# DS172-1_0-A.net
KiCad netlist of a schematic drawn in Altium Designer
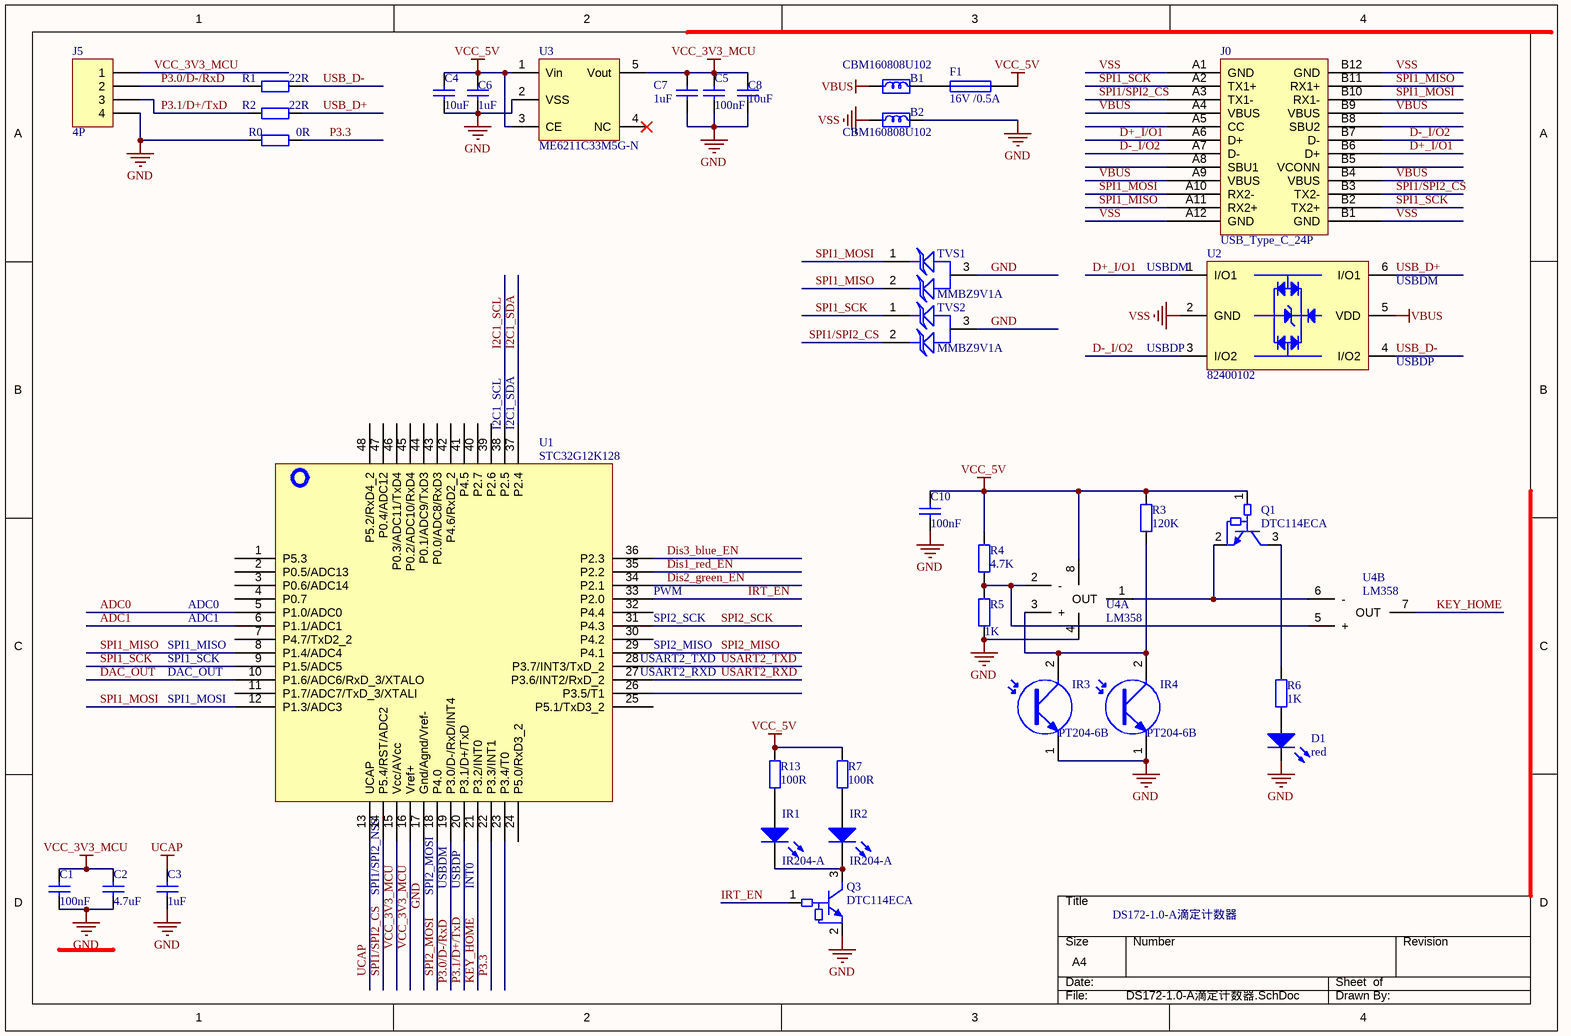
[diagram p0: DS172-1.0-A滴定计数器.SchDoc]

(export (version "E")
  (design (tool "Eeschema 10.0.6"))
  (components
    (comp (ref "B1")
      (value "CBM160808U102")
      (footprint "0603Bead")
      (description "贴片磁珠")
      (libsource (lib "AD_SCH") (part "Chip Ferrite Bead 0606"))
    )
    (comp (ref "B2")
      (value "CBM160808U102")
      (footprint "0603Bead")
      (description "贴片磁珠")
      (libsource (lib "AD_SCH") (part "Chip Ferrite Bead 0606"))
    )
    (comp (ref "C1")
      (value "100nF")
      (footprint "0603CAP")
      (description "贴片电容")
      (fields (field (name "Comment") "SMDCAP00013"))
      (libsource (lib "AD_SCH") (part "MLCC 100nF 50V ±10％ 0603"))
    )
    (comp (ref "C2")
      (value "4.7uF")
      (footprint "0603CAP")
      (description "贴片电容")
      (fields (field (name "Comment") "SMDCAP00012"))
      (libsource (lib "AD_SCH") (part "MLCC 4.7uF 50V ±10％ 0603"))
    )
    (comp (ref "C3")
      (value "1uF")
      (footprint "0603CAP")
      (description "贴片电容")
      (fields (field (name "Comment") "SMDCAP00015"))
      (libsource (lib "AD_SCH") (part "MLCC 1uF 50V ±10％ 0603"))
    )
    (comp (ref "C4")
      (value "10uF")
      (footprint "1206CAP")
      (description "贴片电容")
      (fields (field (name "Comment") "MLCC 10uF 50V ±20％ 1206"))
      (libsource (lib "AD_SCH") (part "MLCC 10uF 50V ±20％ 1206"))
    )
    (comp (ref "C5")
      (value "100nF")
      (footprint "0603CAP")
      (description "贴片电容")
      (fields (field (name "Comment") "SMDCAP00013"))
      (libsource (lib "AD_SCH") (part "MLCC 100nF 50V ±10％ 0603"))
    )
    (comp (ref "C6")
      (value "1uF")
      (footprint "0603CAP")
      (description "贴片电容")
      (fields (field (name "Comment") "SMDCAP00015"))
      (libsource (lib "AD_SCH") (part "MLCC 1uF 50V ±10％ 0603"))
    )
    (comp (ref "C7")
      (value "1uF")
      (footprint "0603CAP")
      (description "贴片电容")
      (fields (field (name "Comment") "SMDCAP00015"))
      (libsource (lib "AD_SCH") (part "MLCC 1uF 50V ±10％ 0603"))
    )
    (comp (ref "C8")
      (value "10uF")
      (footprint "1206CAP")
      (description "贴片电容")
      (fields (field (name "Comment") "MLCC 10uF 50V ±20％ 1206"))
      (libsource (lib "AD_SCH") (part "MLCC 10uF 50V ±20％ 1206"))
    )
    (comp (ref "C10")
      (value "100nF")
      (footprint "0603CAP")
      (description "贴片电容")
      (fields (field (name "Comment") "SMDCAP00013"))
      (libsource (lib "AD_SCH") (part "MLCC 100nF 50V ±10％ 0603"))
    )
    (comp (ref "D1")
      (value "red")
      (footprint "LED_3mm_red")
      (description "插件LED")
      (fields (field (name "Comment") "Φ3 透明发红 DIP2"))
      (libsource (lib "AD_SCH") (part "Φ3 透明发红 DIP2"))
    )
    (comp (ref "F1")
      (value "16V /0.5A")
      (footprint "1206FUSE")
      (description "贴片自恢复保险丝 16V /0.5A")
      (fields (field (name "Comment") "SMD1206-050C-16V"))
      (libsource (lib "AD_SCH") (part "SMD1206-050C-16V"))
    )
    (comp (ref "IR1")
      (value "IR204-A")
      (footprint "LED_IR_W_3mm")
      (description "红外发射管DIP2 Φ3")
      (libsource (lib "AD_SCH") (part "IR204-A"))
    )
    (comp (ref "IR2")
      (value "IR204-A")
      (footprint "LED_IR_W_3mm")
      (description "红外发射管DIP2 Φ3")
      (libsource (lib "AD_SCH") (part "IR204-A"))
    )
    (comp (ref "IR3")
      (value "PT204-6B")
      (footprint "LED_IR_W_3mm")
      (description "红外接收管DIP2 Φ3")
      (fields (field (name "Comment") "SE000000002"))
      (libsource (lib "AD_SCH") (part "PT204-6B"))
    )
    (comp (ref "IR4")
      (value "PT204-6B")
      (footprint "LED_IR_W_3mm")
      (description "红外接收管DIP2 Φ3")
      (fields (field (name "Comment") "SE000000002"))
      (libsource (lib "AD_SCH") (part "PT204-6B"))
    )
    (comp (ref "J0")
      (value "USB_Type_C_24P")
      (footprint "USB_TYPE_C_24P_Receptacle")
      (libsource (lib "AD_SCH") (part "USB_Type_C_24P"))
    )
    (comp (ref "J5")
      (value "4P")
      (footprint "H4")
      (description "单排直针")
      (fields (field (name "Comment") "DIP4单排直针  间距2mm 针长11mm 铜"))
      (libsource (lib "AD_SCH") (part "DIP4单排直针  间距2mm 针长11mm 铜"))
    )
    (comp (ref "Q1")
      (value "DTC114ECA")
      (footprint "SOT23")
      (description "数字晶体管")
      (fields (field (name "Comment") "SMDIC000037"))
      (libsource (lib "AD_SCH") (part "DTC114ECA SOT-23 长电"))
    )
    (comp (ref "Q3")
      (value "DTC114ECA")
      (footprint "SOT23")
      (description "数字晶体管")
      (fields (field (name "Comment") "SMDIC000037"))
      (libsource (lib "") (part "DTC114ECA SOT-23 长电_1"))
    )
    (comp (ref "R0")
      (value "0R")
      (footprint "0603RES")
      (description "贴片电阻")
      (fields (field (name "Comment") "Chip 0R 1/16W ±1％ 0603"))
      (libsource (lib "AD_SCH") (part "Chip 0R 1/16W ±1％ 0603"))
    )
    (comp (ref "R1")
      (value "22R")
      (footprint "0603RES")
      (description "贴片电阻")
      (fields (field (name "Comment") "Chip 22R 1/16W ±1％ 0603"))
      (libsource (lib "AD_SCH") (part "Chip 22R 1/16W ±1％ 0603"))
    )
    (comp (ref "R2")
      (value "22R")
      (footprint "0603RES")
      (description "贴片电阻")
      (fields (field (name "Comment") "Chip 22R 1/16W ±1％ 0603"))
      (libsource (lib "AD_SCH") (part "Chip 22R 1/16W ±1％ 0603"))
    )
    (comp (ref "R3")
      (value "120K")
      (footprint "0603RES")
      (description "贴片电阻")
      (fields (field (name "Comment") "Chip 120K 1/16W ±1％ 0603"))
      (libsource (lib "AD_SCH") (part "Chip 120K 1/16W ±1％ 0603"))
    )
    (comp (ref "R4")
      (value "4.7K")
      (footprint "0603RES")
      (description "贴片电阻")
      (fields (field (name "Comment") "SMDRES00047"))
      (libsource (lib "AD_SCH") (part "Chip 4.7K 1/16W ±1％ 0603"))
    )
    (comp (ref "R5")
      (value "1K")
      (footprint "0603RES")
      (description "贴片电阻")
      (fields (field (name "Comment") "SMDRES00034"))
      (libsource (lib "AD_SCH") (part "Chip 1K 1/16W ±1％ 0603"))
    )
    (comp (ref "R6")
      (value "1K")
      (footprint "0603RES")
      (description "贴片电阻")
      (fields (field (name "Comment") "SMDRES00034"))
      (libsource (lib "AD_SCH") (part "Chip 1K 1/16W ±1％ 0603"))
    )
    (comp (ref "R7")
      (value "100R")
      (footprint "0603RES")
      (description "贴片电阻")
      (fields (field (name "Comment") "SMDRES00015"))
      (libsource (lib "AD_SCH") (part "Chip 100R 1/16W ±1％ 0603"))
    )
    (comp (ref "R13")
      (value "100R")
      (footprint "0603RES")
      (description "贴片电阻")
      (fields (field (name "Comment") "SMDRES00015"))
      (libsource (lib "AD_SCH") (part "Chip 100R 1/16W ±1％ 0603"))
    )
    (comp (ref "TVS1")
      (value "MMBZ9V1A")
      (footprint "SOT23")
      (description "瞬态抑制二极管")
      (libsource (lib "AD_SCH") (part "TVS"))
    )
    (comp (ref "TVS2")
      (value "MMBZ9V1A")
      (footprint "SOT23")
      (description "瞬态抑制二极管")
      (libsource (lib "AD_SCH") (part "TVS"))
    )
    (comp (ref "U1")
      (value "STC32G12K128")
      (footprint "LQFP-48")
      (description "单片机芯片")
      (fields (field (name "Comment") "STC32G12K128_35I LQFP48"))
      (libsource (lib "AD_SCH") (part "STC32G12K128_35I LQFP48"))
    )
    (comp (ref "U2")
      (value "82400102")
      (footprint "SOT23-6")
      (description "瞬态抑制二极管(TVS)")
      (libsource (lib "AD_SCH") (part "82400102"))
    )
    (comp (ref "U3")
      (value "ME6211C33M5G-N")
      (footprint "SOT23-5")
      (description "稳压芯片")
      (libsource (lib "AD_SCH") (part "ME6211C33M5G-N"))
    )
    (comp (ref "U4")
      (value "LM358")
      (footprint "SO-8")
      (description "运放芯片")
      (fields (field (name "Comment") "SMDIC000034"))
      (libsource (lib "AD_SCH") (part "LM358 SOP-8 ST"))
    )
  )
  (nets
    (net (code "1") (name "/ADC0") (class "Default")
      (node (ref "U1") (pin "5") (pinfunction "P1.0/ADC0_5") (pintype "passive"))
    )
    (net (code "2") (name "/ADC1") (class "Default")
      (node (ref "U1") (pin "6") (pinfunction "P1.1/ADC1_6") (pintype "passive"))
    )
    (net (code "3") (name "/D+_I{slash}O1") (class "Default")
      (node (ref "J0") (pin "A6") (pinfunction "D+_A6") (pintype "passive"))
      (node (ref "J0") (pin "B6") (pinfunction "D+_B6") (pintype "passive"))
      (node (ref "U2") (pin "1") (pinfunction "I/O1_1") (pintype "passive"))
    )
    (net (code "4") (name "/D-_I{slash}O2") (class "Default")
      (node (ref "J0") (pin "A7") (pinfunction "D-_A7") (pintype "passive"))
      (node (ref "J0") (pin "B7") (pinfunction "D-_B7") (pintype "passive"))
      (node (ref "U2") (pin "3") (pinfunction "I/O2_3") (pintype "passive"))
    )
    (net (code "5") (name "/DAC_OUT") (class "Default")
      (node (ref "U1") (pin "10") (pinfunction "P1.6/ADC6/RxD_3/XTALO_10") (pintype "passive"))
    )
    (net (code "6") (name "/Dis1_red_EN") (class "Default")
      (node (ref "U1") (pin "35") (pinfunction "P2.2_35") (pintype "passive"))
    )
    (net (code "7") (name "/Dis2_green_EN") (class "Default")
      (node (ref "U1") (pin "34") (pinfunction "P2.1_34") (pintype "passive"))
    )
    (net (code "8") (name "/Dis3_blue_EN") (class "Default")
      (node (ref "U1") (pin "36") (pinfunction "P2.3_36") (pintype "passive"))
    )
    (net (code "9") (name "/I2C1_SCL") (class "Default")
      (node (ref "U1") (pin "38") (pinfunction "P2.5_38") (pintype "passive"))
    )
    (net (code "10") (name "/I2C1_SDA") (class "Default")
      (node (ref "U1") (pin "37") (pinfunction "P2.4_37") (pintype "passive"))
    )
    (net (code "11") (name "/IRT_EN") (class "Default")
      (node (ref "Q3") (pin "1") (pinfunction "IN_1") (pintype "passive"))
      (node (ref "U1") (pin "33") (pinfunction "P2.0_33") (pintype "passive"))
    )
    (net (code "12") (name "/KEY_HOME") (class "Default")
      (node (ref "U1") (pin "21") (pinfunction "P3.2/INT0_21") (pintype "passive"))
      (node (ref "U4") (pin "7") (pinfunction "OUT_7") (pintype "passive"))
    )
    (net (code "13") (name "/P3.0{slash}D-{slash}RxD") (class "Default")
      (node (ref "J5") (pin "2") (pinfunction "2_2") (pintype "passive"))
      (node (ref "R1") (pin "1") (pinfunction "1_1") (pintype "passive"))
      (node (ref "U1") (pin "19") (pinfunction "P3.0/D-/RxD/INT4_19") (pintype "passive"))
    )
    (net (code "14") (name "/P3.1{slash}D+{slash}TxD") (class "Default")
      (node (ref "J5") (pin "3") (pinfunction "3_3") (pintype "passive"))
      (node (ref "R2") (pin "1") (pinfunction "1_1") (pintype "passive"))
      (node (ref "U1") (pin "20") (pinfunction "P3.1/D+/TxD_20") (pintype "passive"))
    )
    (net (code "15") (name "/P3.3") (class "Default")
      (node (ref "R0") (pin "2") (pinfunction "2_2") (pintype "passive"))
      (node (ref "U1") (pin "22") (pinfunction "P3.3/INT1_22") (pintype "passive"))
    )
    (net (code "16") (name "/SPI1_MISO") (class "Default")
      (node (ref "J0") (pin "A11") (pinfunction "RX2+_A11") (pintype "passive"))
      (node (ref "J0") (pin "B11") (pinfunction "RX1+_B11") (pintype "passive"))
      (node (ref "TVS1") (pin "2") (pinfunction "2_2") (pintype "passive"))
      (node (ref "U1") (pin "8") (pinfunction "P1.4/ADC4_8") (pintype "passive"))
    )
    (net (code "17") (name "/SPI1_MOSI") (class "Default")
      (node (ref "J0") (pin "A10") (pinfunction "RX2-_A10") (pintype "passive"))
      (node (ref "J0") (pin "B10") (pinfunction "RX1-_B10") (pintype "passive"))
      (node (ref "TVS1") (pin "1") (pinfunction "1_1") (pintype "passive"))
      (node (ref "U1") (pin "12") (pinfunction "P1.3/ADC3_12") (pintype "passive"))
    )
    (net (code "18") (name "/SPI1_SCK") (class "Default")
      (node (ref "J0") (pin "A2") (pinfunction "TX1+_A2") (pintype "passive"))
      (node (ref "J0") (pin "B2") (pinfunction "TX2+_B2") (pintype "passive"))
      (node (ref "TVS2") (pin "1") (pinfunction "1_1") (pintype "passive"))
      (node (ref "U1") (pin "9") (pinfunction "P1.5/ADC5_9") (pintype "passive"))
    )
    (net (code "19") (name "/SPI1{slash}SPI2_CS") (class "Default")
      (node (ref "J0") (pin "A3") (pinfunction "TX1-_A3") (pintype "passive"))
      (node (ref "J0") (pin "B3") (pinfunction "TX2-_B3") (pintype "passive"))
      (node (ref "TVS2") (pin "2") (pinfunction "2_2") (pintype "passive"))
      (node (ref "U1") (pin "14") (pinfunction "P5.4/RST/ADC2_14") (pintype "passive"))
    )
    (net (code "20") (name "/SPI2_MISO") (class "Default")
      (node (ref "U1") (pin "29") (pinfunction "P4.1_29") (pintype "passive"))
    )
    (net (code "21") (name "/SPI2_MOSI") (class "Default")
      (node (ref "U1") (pin "18") (pinfunction "P4.0_18") (pintype "passive"))
    )
    (net (code "22") (name "/SPI2_SCK") (class "Default")
      (node (ref "U1") (pin "31") (pinfunction "P4.3_31") (pintype "passive"))
    )
    (net (code "23") (name "/USART2_RXD") (class "Default")
      (node (ref "U1") (pin "27") (pinfunction "P3.6/INT2/RxD_2_27") (pintype "passive"))
    )
    (net (code "24") (name "/USART2_TXD") (class "Default")
      (node (ref "U1") (pin "28") (pinfunction "P3.7/INT3/TxD_2_28") (pintype "passive"))
    )
    (net (code "25") (name "/USB_D+") (class "Default")
      (node (ref "R2") (pin "2") (pinfunction "2_2") (pintype "passive"))
      (node (ref "U2") (pin "6") (pinfunction "I/O1_6") (pintype "passive"))
    )
    (net (code "26") (name "/USB_D-") (class "Default")
      (node (ref "R1") (pin "2") (pinfunction "2_2") (pintype "passive"))
      (node (ref "U2") (pin "4") (pinfunction "I/O2_4") (pintype "passive"))
    )
    (net (code "27") (name "GND") (class "Default")
      (node (ref "B2") (pin "2") (pinfunction "2_2") (pintype "passive"))
      (node (ref "C1") (pin "1") (pinfunction "1_1") (pintype "passive"))
      (node (ref "C10") (pin "1") (pinfunction "1_1") (pintype "passive"))
      (node (ref "C2") (pin "1") (pinfunction "1_1") (pintype "passive"))
      (node (ref "C3") (pin "1") (pinfunction "1_1") (pintype "passive"))
      (node (ref "C4") (pin "1") (pinfunction "1_1") (pintype "passive"))
      (node (ref "C5") (pin "1") (pinfunction "1_1") (pintype "passive"))
      (node (ref "C6") (pin "1") (pinfunction "1_1") (pintype "passive"))
      (node (ref "C7") (pin "1") (pinfunction "1_1") (pintype "passive"))
      (node (ref "C8") (pin "1") (pinfunction "1_1") (pintype "passive"))
      (node (ref "D1") (pin "2") (pinfunction "K_2") (pintype "passive"))
      (node (ref "IR3") (pin "1") (pinfunction "E_1") (pintype "passive"))
      (node (ref "IR4") (pin "1") (pinfunction "E_1") (pintype "passive"))
      (node (ref "J5") (pin "4") (pinfunction "4_4") (pintype "passive"))
      (node (ref "Q3") (pin "2") (pinfunction "GND_2") (pintype "passive"))
      (node (ref "R0") (pin "1") (pinfunction "1_1") (pintype "passive"))
      (node (ref "R5") (pin "1") (pinfunction "1_1") (pintype "passive"))
      (node (ref "TVS1") (pin "3") (pinfunction "3_3") (pintype "passive"))
      (node (ref "TVS2") (pin "3") (pinfunction "3_3") (pintype "passive"))
      (node (ref "U1") (pin "17") (pinfunction "Gnd/Agnd/Vref-_17") (pintype "passive"))
      (node (ref "U3") (pin "2") (pinfunction "VSS_2") (pintype "passive"))
      (node (ref "U4") (pin "4") (pinfunction "GND_4") (pintype "passive"))
    )
    (net (code "28") (name "Net-(B1-Pad2)") (class "Default")
      (node (ref "B1") (pin "2") (pinfunction "2_2") (pintype "passive"))
      (node (ref "F1") (pin "1") (pinfunction "1_1") (pintype "passive"))
    )
    (net (code "29") (name "Net-(D1-A)") (class "Default")
      (node (ref "D1") (pin "1") (pinfunction "A_1") (pintype "passive"))
      (node (ref "R6") (pin "1") (pinfunction "1_1") (pintype "passive"))
    )
    (net (code "30") (name "Net-(IR1-A)") (class "Default")
      (node (ref "IR1") (pin "1") (pinfunction "A_1") (pintype "passive"))
      (node (ref "R13") (pin "1") (pinfunction "1_1") (pintype "passive"))
    )
    (net (code "31") (name "Net-(IR1-K)") (class "Default")
      (node (ref "IR1") (pin "2") (pinfunction "K_2") (pintype "passive"))
      (node (ref "IR2") (pin "2") (pinfunction "K_2") (pintype "passive"))
      (node (ref "Q3") (pin "3") (pinfunction "OUT_3") (pintype "passive"))
    )
    (net (code "32") (name "Net-(IR2-A)") (class "Default")
      (node (ref "IR2") (pin "1") (pinfunction "A_1") (pintype "passive"))
      (node (ref "R7") (pin "1") (pinfunction "1_1") (pintype "passive"))
    )
    (net (code "33") (name "Net-(IR3-C)") (class "Default")
      (node (ref "IR3") (pin "2") (pinfunction "C_2") (pintype "passive"))
      (node (ref "IR4") (pin "2") (pinfunction "C_2") (pintype "passive"))
      (node (ref "R3") (pin "1") (pinfunction "1_1") (pintype "passive"))
      (node (ref "U4") (pin "3") (pinfunction "+_3") (pintype "passive"))
    )
    (net (code "34") (name "Net-(Q1-GND)") (class "Default")
      (node (ref "Q1") (pin "2") (pinfunction "GND_2") (pintype "passive"))
      (node (ref "U4") (pin "1") (pinfunction "OUT_1") (pintype "passive"))
      (node (ref "U4") (pin "6") (pinfunction "-_6") (pintype "passive"))
    )
    (net (code "35") (name "Net-(Q1-OUT)") (class "Default")
      (node (ref "Q1") (pin "3") (pinfunction "OUT_3") (pintype "passive"))
      (node (ref "R6") (pin "2") (pinfunction "2_2") (pintype "passive"))
    )
    (net (code "36") (name "Net-(U4A--)") (class "Default")
      (node (ref "R4") (pin "1") (pinfunction "1_1") (pintype "passive"))
      (node (ref "R5") (pin "2") (pinfunction "2_2") (pintype "passive"))
      (node (ref "U4") (pin "2") (pinfunction "-_2") (pintype "passive"))
      (node (ref "U4") (pin "5") (pinfunction "+_5") (pintype "passive"))
    )
    (net (code "37") (name "UCAP") (class "Default")
      (node (ref "C3") (pin "2") (pinfunction "2_2") (pintype "passive"))
      (node (ref "U1") (pin "13") (pinfunction "UCAP_13") (pintype "passive"))
    )
    (net (code "38") (name "VBUS") (class "Default")
      (node (ref "B1") (pin "1") (pinfunction "1_1") (pintype "passive"))
      (node (ref "J0") (pin "A4") (pinfunction "VBUS_A4") (pintype "passive"))
      (node (ref "J0") (pin "A9") (pinfunction "VBUS_A9") (pintype "passive"))
      (node (ref "J0") (pin "B4") (pinfunction "VBUS_B4") (pintype "passive"))
      (node (ref "J0") (pin "B9") (pinfunction "VBUS_B9") (pintype "passive"))
      (node (ref "U2") (pin "5") (pinfunction "VDD_5") (pintype "passive"))
    )
    (net (code "39") (name "VCC_3V3_MCU") (class "Default")
      (node (ref "C1") (pin "2") (pinfunction "2_2") (pintype "passive"))
      (node (ref "C2") (pin "2") (pinfunction "2_2") (pintype "passive"))
      (node (ref "C5") (pin "2") (pinfunction "2_2") (pintype "passive"))
      (node (ref "C7") (pin "2") (pinfunction "2_2") (pintype "passive"))
      (node (ref "C8") (pin "2") (pinfunction "2_2") (pintype "passive"))
      (node (ref "J5") (pin "1") (pinfunction "1_1") (pintype "passive"))
      (node (ref "U1") (pin "15") (pinfunction "Vcc/AVcc_15") (pintype "passive"))
      (node (ref "U1") (pin "16") (pinfunction "Vref+_16") (pintype "passive"))
      (node (ref "U3") (pin "5") (pinfunction "Vout_5") (pintype "passive"))
    )
    (net (code "40") (name "VCC_5V") (class "Default")
      (node (ref "C10") (pin "2") (pinfunction "2_2") (pintype "passive"))
      (node (ref "C4") (pin "2") (pinfunction "2_2") (pintype "passive"))
      (node (ref "C6") (pin "2") (pinfunction "2_2") (pintype "passive"))
      (node (ref "F1") (pin "2") (pinfunction "2_2") (pintype "passive"))
      (node (ref "Q1") (pin "1") (pinfunction "IN_1") (pintype "passive"))
      (node (ref "R13") (pin "2") (pinfunction "2_2") (pintype "passive"))
      (node (ref "R3") (pin "2") (pinfunction "2_2") (pintype "passive"))
      (node (ref "R4") (pin "2") (pinfunction "2_2") (pintype "passive"))
      (node (ref "R7") (pin "2") (pinfunction "2_2") (pintype "passive"))
      (node (ref "U3") (pin "1") (pinfunction "Vin_1") (pintype "passive"))
      (node (ref "U3") (pin "3") (pinfunction "CE_3") (pintype "passive"))
      (node (ref "U4") (pin "8") (pinfunction "VCC_8") (pintype "passive"))
    )
    (net (code "41") (name "VSS") (class "Default")
      (node (ref "B2") (pin "1") (pinfunction "1_1") (pintype "passive"))
      (node (ref "J0") (pin "A1") (pinfunction "GND_A1") (pintype "passive"))
      (node (ref "J0") (pin "A12") (pinfunction "GND_A12") (pintype "passive"))
      (node (ref "J0") (pin "B1") (pinfunction "GND_B1") (pintype "passive"))
      (node (ref "J0") (pin "B12") (pinfunction "GND_B12") (pintype "passive"))
      (node (ref "U2") (pin "2") (pinfunction "GND_2") (pintype "passive"))
    )
    (net (code "42") (name "unconnected-(J0-CC-PadA5)") (class "Default")
      (node (ref "J0") (pin "A5") (pinfunction "CC_A5") (pintype "passive"))
    )
    (net (code "43") (name "unconnected-(J0-SBU1-PadA8)") (class "Default")
      (node (ref "J0") (pin "A8") (pinfunction "SBU1_A8") (pintype "passive"))
    )
    (net (code "44") (name "unconnected-(J0-SBU2-PadB8)") (class "Default")
      (node (ref "J0") (pin "B8") (pinfunction "SBU2_B8") (pintype "passive"))
    )
    (net (code "45") (name "unconnected-(J0-VCONN-PadB5)") (class "Default")
      (node (ref "J0") (pin "B5") (pinfunction "VCONN_B5") (pintype "passive"))
    )
    (net (code "46") (name "unconnected-(U1-P0.0{slash}ADC8{slash}RxD3-Pad43)") (class "Default")
      (node (ref "U1") (pin "43") (pinfunction "P0.0/ADC8/RxD3_43") (pintype "passive"))
    )
    (net (code "47") (name "unconnected-(U1-P0.1{slash}ADC9{slash}TxD3-Pad44)") (class "Default")
      (node (ref "U1") (pin "44") (pinfunction "P0.1/ADC9/TxD3_44") (pintype "passive"))
    )
    (net (code "48") (name "unconnected-(U1-P0.2{slash}ADC10{slash}RxD4-Pad45)") (class "Default")
      (node (ref "U1") (pin "45") (pinfunction "P0.2/ADC10/RxD4_45") (pintype "passive"))
    )
    (net (code "49") (name "unconnected-(U1-P0.3{slash}ADC11{slash}TxD4-Pad46)") (class "Default")
      (node (ref "U1") (pin "46") (pinfunction "P0.3/ADC11/TxD4_46") (pintype "passive"))
    )
    (net (code "50") (name "unconnected-(U1-P0.4{slash}ADC12-Pad47)") (class "Default")
      (node (ref "U1") (pin "47") (pinfunction "P0.4/ADC12_47") (pintype "passive"))
    )
    (net (code "51") (name "unconnected-(U1-P0.5{slash}ADC13-Pad2)") (class "Default")
      (node (ref "U1") (pin "2") (pinfunction "P0.5/ADC13_2") (pintype "passive"))
    )
    (net (code "52") (name "unconnected-(U1-P0.6{slash}ADC14-Pad3)") (class "Default")
      (node (ref "U1") (pin "3") (pinfunction "P0.6/ADC14_3") (pintype "passive"))
    )
    (net (code "53") (name "unconnected-(U1-P0.7-Pad4)") (class "Default")
      (node (ref "U1") (pin "4") (pinfunction "P0.7_4") (pintype "passive"))
    )
    (net (code "54") (name "unconnected-(U1-P1.7{slash}ADC7{slash}TxD_3{slash}XTALI-Pad11)") (class "Default")
      (node (ref "U1") (pin "11") (pinfunction "P1.7/ADC7/TxD_3/XTALI_11") (pintype "passive"))
    )
    (net (code "55") (name "unconnected-(U1-P2.6-Pad39)") (class "Default")
      (node (ref "U1") (pin "39") (pinfunction "P2.6_39") (pintype "passive"))
    )
    (net (code "56") (name "unconnected-(U1-P2.7-Pad40)") (class "Default")
      (node (ref "U1") (pin "40") (pinfunction "P2.7_40") (pintype "passive"))
    )
    (net (code "57") (name "unconnected-(U1-P3.4{slash}T0-Pad23)") (class "Default")
      (node (ref "U1") (pin "23") (pinfunction "P3.4/T0_23") (pintype "passive"))
    )
    (net (code "58") (name "unconnected-(U1-P3.5{slash}T1-Pad26)") (class "Default")
      (node (ref "U1") (pin "26") (pinfunction "P3.5/T1_26") (pintype "passive"))
    )
    (net (code "59") (name "unconnected-(U1-P4.2-Pad30)") (class "Default")
      (node (ref "U1") (pin "30") (pinfunction "P4.2_30") (pintype "passive"))
    )
    (net (code "60") (name "unconnected-(U1-P4.4-Pad32)") (class "Default")
      (node (ref "U1") (pin "32") (pinfunction "P4.4_32") (pintype "passive"))
    )
    (net (code "61") (name "unconnected-(U1-P4.5-Pad41)") (class "Default")
      (node (ref "U1") (pin "41") (pinfunction "P4.5_41") (pintype "passive"))
    )
    (net (code "62") (name "unconnected-(U1-P4.6{slash}RxD2_2-Pad42)") (class "Default")
      (node (ref "U1") (pin "42") (pinfunction "P4.6/RxD2_2_42") (pintype "passive"))
    )
    (net (code "63") (name "unconnected-(U1-P4.7{slash}TxD2_2-Pad7)") (class "Default")
      (node (ref "U1") (pin "7") (pinfunction "P4.7/TxD2_2_7") (pintype "passive"))
    )
    (net (code "64") (name "unconnected-(U1-P5.0{slash}RxD3_2-Pad24)") (class "Default")
      (node (ref "U1") (pin "24") (pinfunction "P5.0/RxD3_2_24") (pintype "passive"))
    )
    (net (code "65") (name "unconnected-(U1-P5.1{slash}TxD3_2-Pad25)") (class "Default")
      (node (ref "U1") (pin "25") (pinfunction "P5.1/TxD3_2_25") (pintype "passive"))
    )
    (net (code "66") (name "unconnected-(U1-P5.2{slash}RxD4_2-Pad48)") (class "Default")
      (node (ref "U1") (pin "48") (pinfunction "P5.2/RxD4_2_48") (pintype "passive"))
    )
    (net (code "67") (name "unconnected-(U1-P5.3-Pad1)") (class "Default")
      (node (ref "U1") (pin "1") (pinfunction "P5.3_1") (pintype "passive"))
    )
    (net (code "68") (name "unconnected-(U3-NC-Pad4)") (class "Default")
      (node (ref "U3") (pin "4") (pinfunction "NC_4") (pintype "passive+no_connect"))
    )
  )
)
